# FRONT-UNIT-3_2-WIDE.net
KiCad netlist of a schematic drawn in Altium Designer
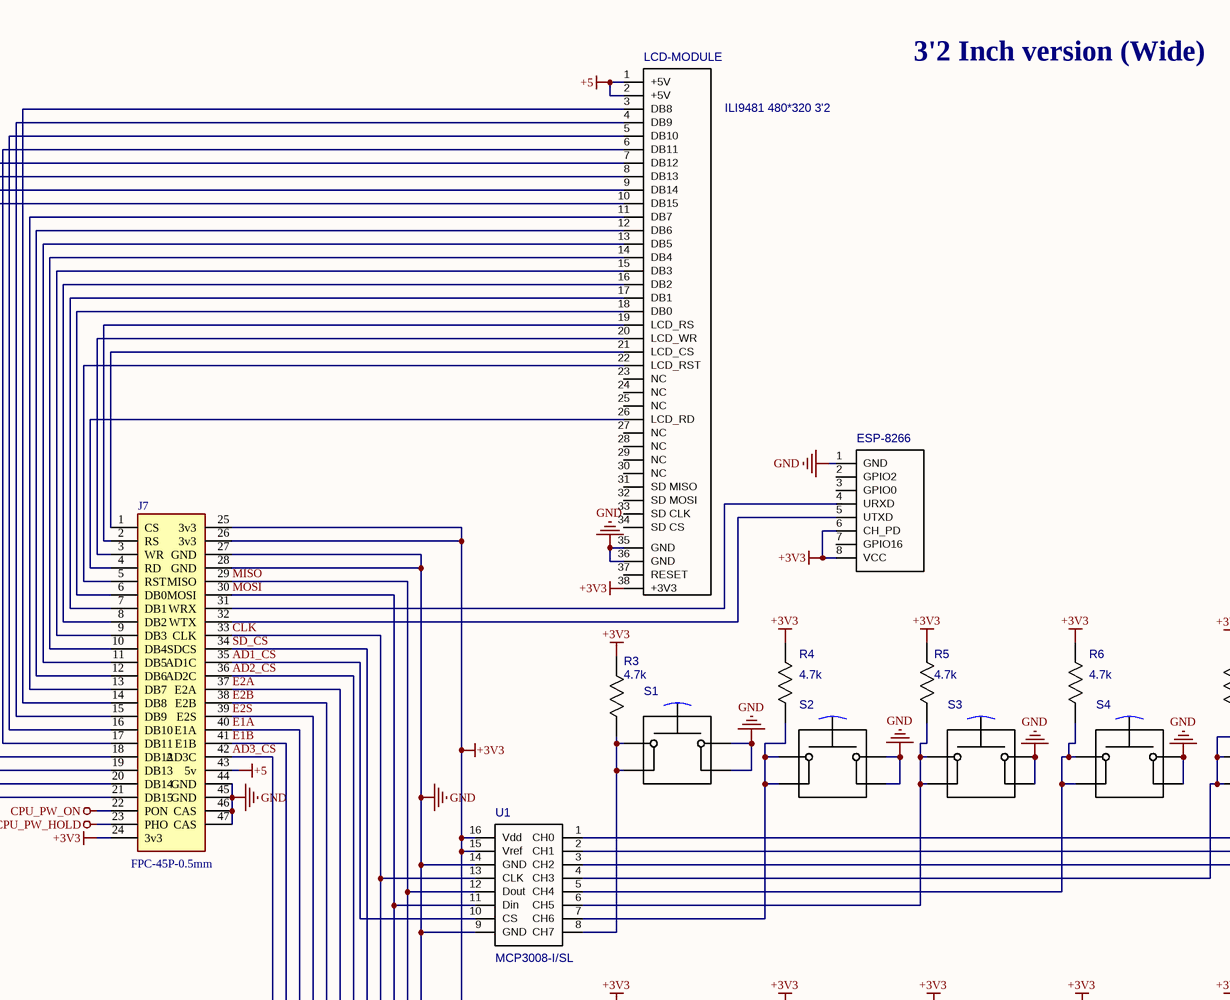
[diagram p0: FRONT-UNIT-3.2-WIDE.SCHDOC, top left]
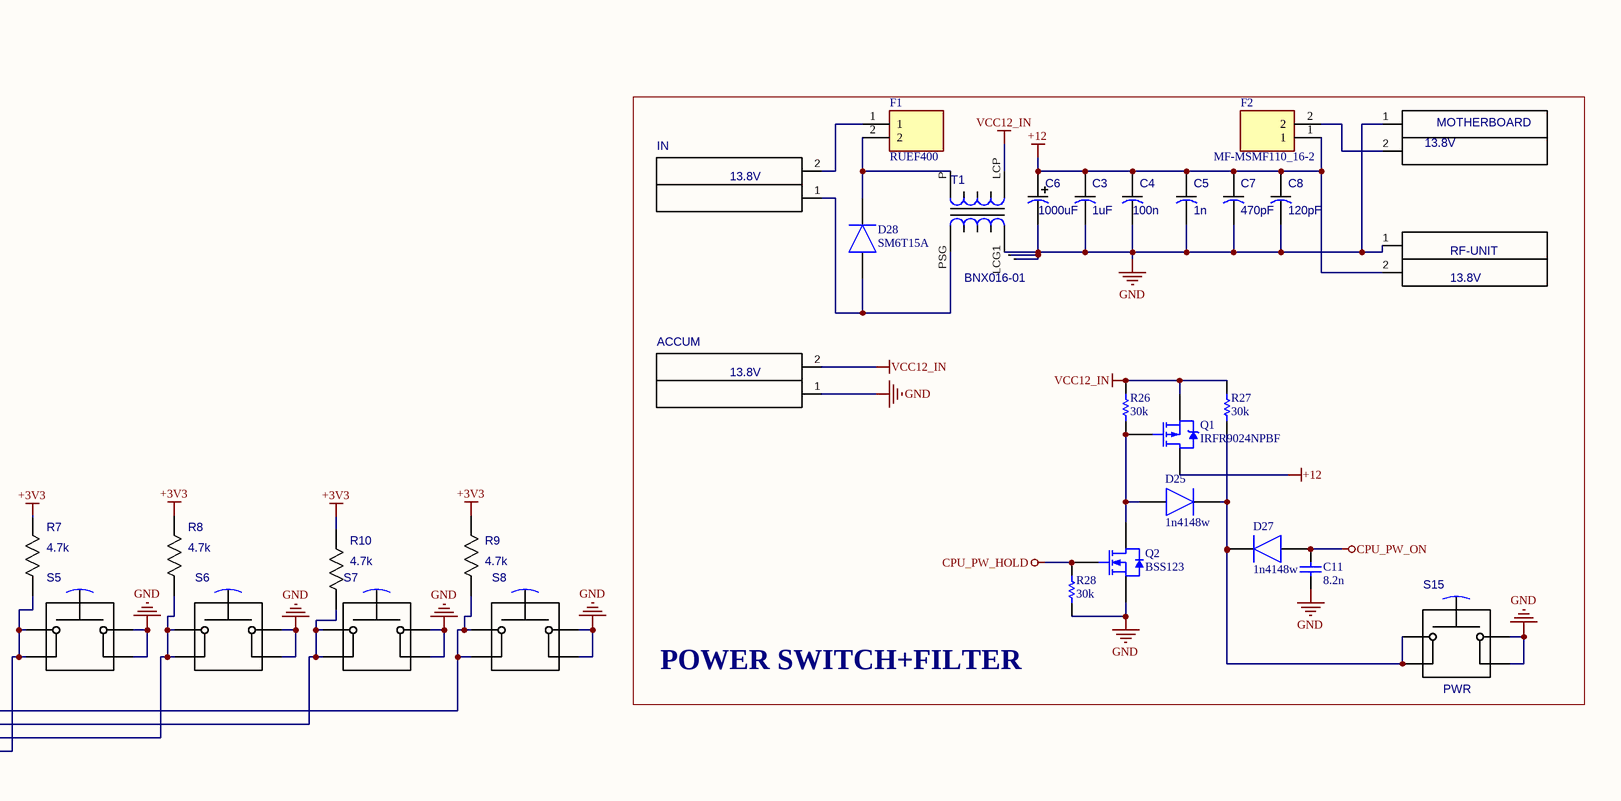
[diagram p1: FRONT-UNIT-3.2-WIDE.SCHDOC, top right]
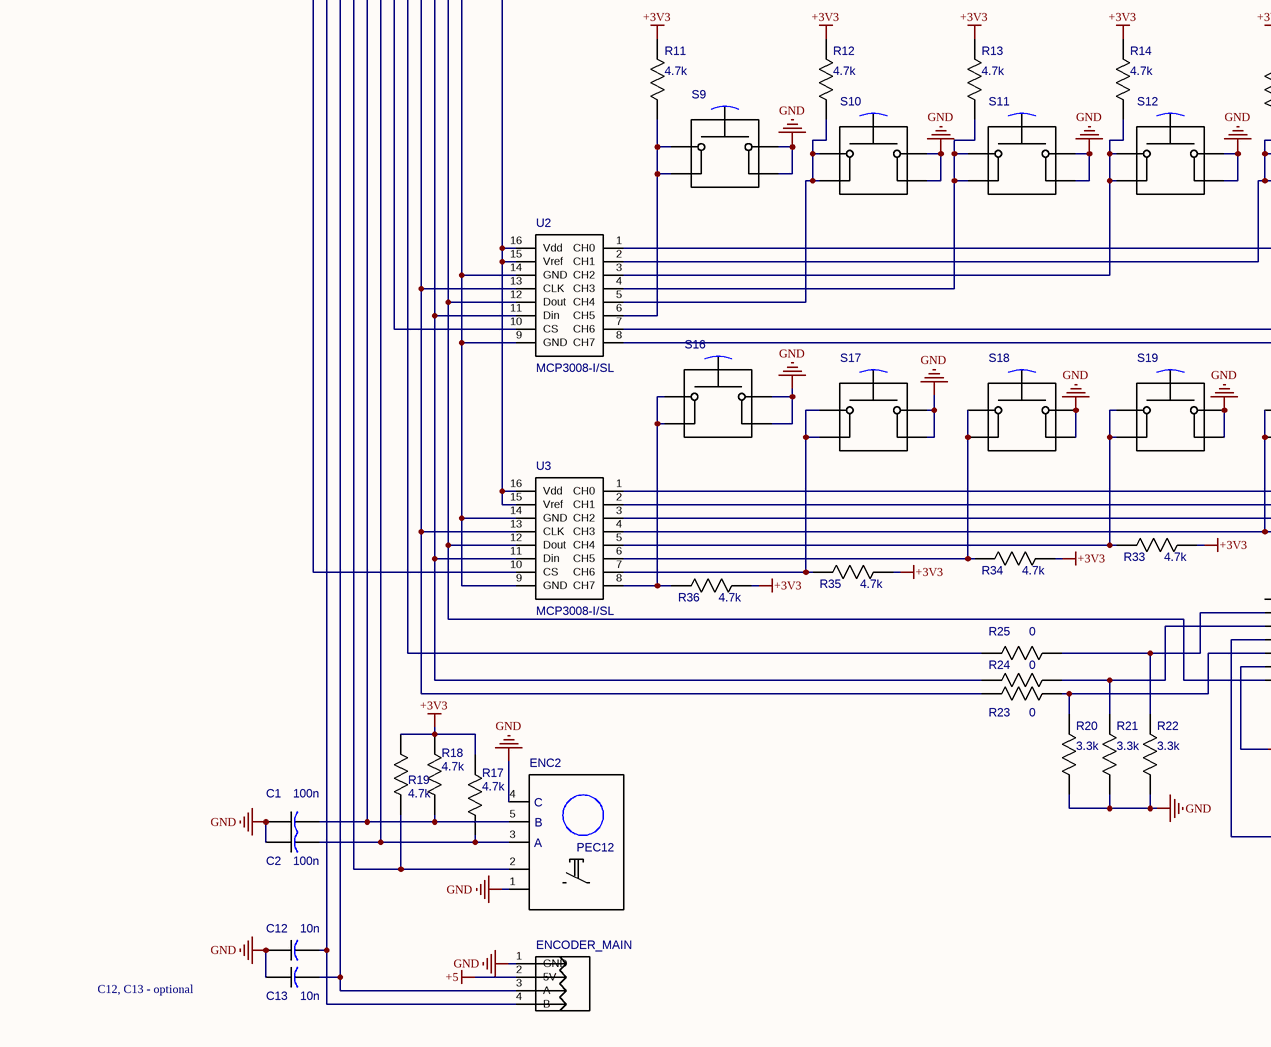
[diagram p2: FRONT-UNIT-3.2-WIDE.SCHDOC, bottom left]
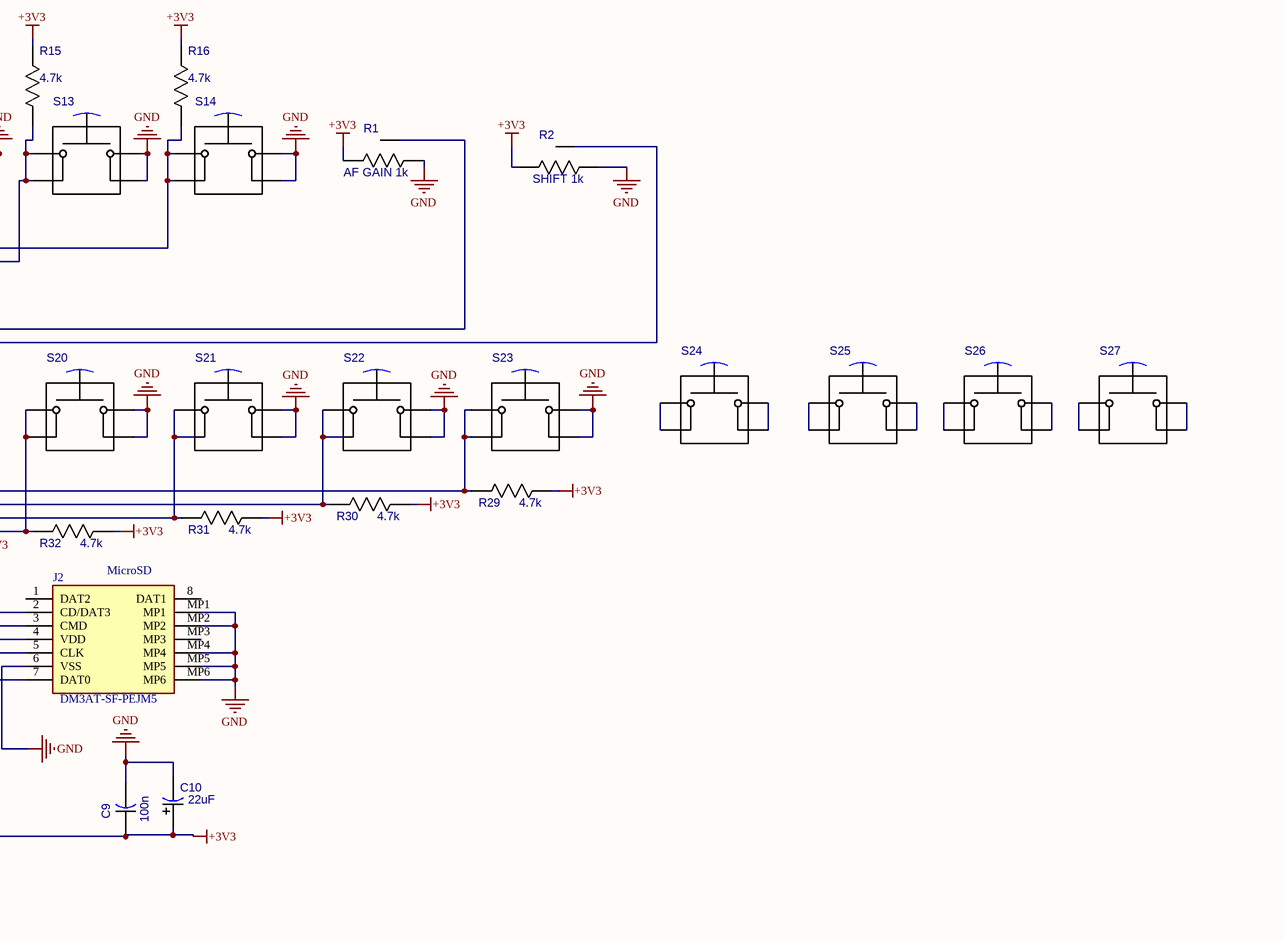
[diagram p3: FRONT-UNIT-3.2-WIDE.SCHDOC, bottom right]

(export (version "E")
  (design (tool "Eeschema 10.0.6"))
  (components
    (comp (ref "ACCUM")
      (value "13.8V")
      (footprint "JX2")
      (description "JX2")
      (libsource (lib "*") (part "JX2"))
    )
    (comp (ref "C1")
      (value "100n")
      (footprint "CAP_0805")
      (description "CAP_0805")
      (libsource (lib "*") (part "CAP_0805"))
    )
    (comp (ref "C2")
      (value "100n")
      (footprint "CAP_0805")
      (description "CAP_0805")
      (libsource (lib "*") (part "CAP_0805"))
    )
    (comp (ref "C3")
      (value "1uF")
      (footprint "CAP_1206")
      (description "CAP_1206")
      (libsource (lib "*") (part "CAP_1206"))
    )
    (comp (ref "C4")
      (value "100n")
      (footprint "CAP_1206")
      (description "CAP_1206")
      (libsource (lib "*") (part "CAP_1206"))
    )
    (comp (ref "C5")
      (value "1n")
      (footprint "CAP_1206")
      (description "CAP_1206")
      (libsource (lib "*") (part "CAP_1206"))
    )
    (comp (ref "C6")
      (value "1000uF")
      (footprint "CAP250RP")
      (description "CAP250RP")
      (libsource (lib "*") (part "CAP250RP"))
    )
    (comp (ref "C7")
      (value "470pF")
      (footprint "CAP_1206")
      (description "CAP_1206")
      (libsource (lib "*") (part "CAP_1206"))
    )
    (comp (ref "C8")
      (value "120pF")
      (footprint "CAP_1206")
      (description "CAP_1206")
      (libsource (lib "*") (part "CAP_1206"))
    )
    (comp (ref "C9")
      (value "100n")
      (footprint "CAP_0805")
      (description "CAP_0805")
      (libsource (lib "*") (part "CAP_0805"))
    )
    (comp (ref "C10")
      (value "22uF")
      (footprint "EEEFC_sizeB")
      (description "EEEFC_sizeB")
      (libsource (lib "*") (part "EEEFC_sizeB"))
    )
    (comp (ref "C11")
      (value "8.2n")
      (footprint "CAPC2013X94X50LL20T25")
      (description "CAP_1206")
      (fields
        (field (name "MANUFACTURER") "AVX Interconnect / Elco")
        (field (name "PART NUMBER") "08055C822KAT2A")
      )
      (libsource (lib "Altium Content Vault") (part "CAP"))
    )
    (comp (ref "C12")
      (value "10n")
      (footprint "CAP_0805")
      (description "CAP_0805")
      (libsource (lib "*") (part "CAP_0805"))
    )
    (comp (ref "C13")
      (value "10n")
      (footprint "CAP_0805")
      (description "CAP_0805")
      (libsource (lib "*") (part "CAP_0805"))
    )
    (comp (ref "D25")
      (value "1n4148w")
      (footprint "SamacSys:SOD3716X135N")
      (description "Diode")
      (libsource (lib "*") (part "1n4148w"))
    )
    (comp (ref "D27")
      (value "1n4148w")
      (footprint "SamacSys:SOD3716X135N")
      (description "Diode")
      (libsource (lib "*") (part "1n4148w"))
    )
    (comp (ref "D28")
      (value "SM6T15A")
      (footprint "SamacSys:SMBJ36CATR")
      (description "Diode")
      (fields (field (name "MOUSER PART NUMBER") "511-SM6T15A") (field (name "RS PART NUMBER") "4864915P"))
      (libsource (lib "*") (part "SM6T15A"))
    )
    (comp (ref "ENC2") (value "PEC12") (footprint "PEC12") (libsource (lib "*") (part "PEC12")))
    (comp (ref "ENCODER_MAIN")
      (value "OPTICAL ENCODER")
      (footprint "644456-4")
      (libsource (lib "*") (part "644456-4"))
    )
    (comp (ref "ESP-8266")
      (value "ESP-01 ESP8266")
      (footprint "ESP-01 ESP8266")
      (libsource (lib "*") (part "ESP-01 ESP8266"))
    )
    (comp (ref "F1")
      (value "RUEF400")
      (footprint "SamacSys:RUEF400")
      (description "Fuse")
      (fields (field (name "MOUSER PART NUMBER") "650-RUEF400") (field (name "RS PART NUMBER") "5176837P"))
      (libsource (lib "*") (part "RUEF400"))
    )
    (comp (ref "F2")
      (value "MF-MSMF110_16-2")
      (footprint "SamacSys:FUSC4632X85N")
      (description "Fuse")
      (fields
        (field (name "MANUFACTURER_PART_NUMBER") "MF-MSMF110/16-2")
        (field (name "MOUSER PART NUMBER") "652-MF-MSMF110/16-2")
      )
      (libsource (lib "*") (part "MF-MSMF110_16-2"))
    )
    (comp (ref "IN") (value "13.8V") (footprint "JX2") (description "JX2") (libsource (lib "*") (part "JX2")))
    (comp (ref "J2")
      (value "DM3AT-SF-PEJM5")
      (footprint "SamacSys:DM3ATSFPEJM5")
      (description "Connector")
      (libsource (lib "*") (part "DM3AT-SF-PEJM5"))
    )
    (comp (ref "J7")
      (value "FPC-45P-0.5mm")
      (footprint "FRONT-UNIT-WIDE:FH12S45S05SH60")
      (description "Connector")
      (fields
        (field (name "MANUFACTURER_PART_NUMBER") "FH12S-45S-0.5SH(55)")
        (field (name "MOUSER PART NUMBER") "798-FH12S-45S-05SH55")
      )
      (libsource (lib "*") (part "FH12S-45S-0.5SH_55_"))
    )
    (comp (ref "LCD-MODULE")
      (value "ILI9481 480*320 3'2")
      (footprint "LCD-MODULE-3.2-480-320")
      (description "LCD-MODULE_3'2_480х320")
      (libsource (lib "FRONT-UNIT") (part "LCD-MODULE_3'2_480х320"))
    )
    (comp (ref "MOTHERBOARD")
      (value "13.8V")
      (footprint "JX2")
      (description "JX2")
      (libsource (lib "*") (part "JX2"))
    )
    (comp (ref "Q1")
      (value "IRFR9024NPBF")
      (footprint "ONSC-DPAK-3-369C-01_V")
      (description "IRFR9024NPBF, Транзистор, Р-канал 55В 11А")
      (fields (field (name "MANUFACTURER") "On Semiconductor") (field (name "PARTNUMBER") "NTD2955G"))
      (libsource (lib "Altium Content Vault") (part "ONSC-PMOS-G1S3D4-3_B"))
    )
    (comp (ref "Q2")
      (value "BSS123")
      (footprint "FAIR-SOT23-3_V")
      (fields (field (name "MANUFACTURER") "Fairchild"))
      (libsource (lib "Altium Content Vault") (part "NEMOS-GSD-3"))
    )
    (comp (ref "R1")
      (value "AF GAIN 1k")
      (footprint "PTV09")
      (description "Adjustable Resistor PTV09")
      (fields (field (name "Comment") "ptv09a-4225f-b102"))
      (libsource (lib "*") (part "PTV09"))
    )
    (comp (ref "R2")
      (value "SHIFT 1k")
      (footprint "PTV09")
      (description "Adjustable Resistor PTV09")
      (fields (field (name "Comment") "ptv09a-4225f-b102"))
      (libsource (lib "*") (part "PTV09"))
    )
    (comp (ref "R3")
      (value "4.7k")
      (footprint "RES_0805")
      (description "RES_0805")
      (libsource (lib "*") (part "RES_0805"))
    )
    (comp (ref "R4")
      (value "4.7k")
      (footprint "RES_0805")
      (description "RES_0805")
      (libsource (lib "*") (part "RES_0805"))
    )
    (comp (ref "R5")
      (value "4.7k")
      (footprint "RES_0805")
      (description "RES_0805")
      (libsource (lib "*") (part "RES_0805"))
    )
    (comp (ref "R6")
      (value "4.7k")
      (footprint "RES_0805")
      (description "RES_0805")
      (libsource (lib "*") (part "RES_0805"))
    )
    (comp (ref "R7")
      (value "4.7k")
      (footprint "RES_0805")
      (description "RES_0805")
      (libsource (lib "*") (part "RES_0805"))
    )
    (comp (ref "R8")
      (value "4.7k")
      (footprint "RES_0805")
      (description "RES_0805")
      (libsource (lib "*") (part "RES_0805"))
    )
    (comp (ref "R9")
      (value "4.7k")
      (footprint "RES_0805")
      (description "RES_0805")
      (libsource (lib "*") (part "RES_0805"))
    )
    (comp (ref "R10")
      (value "4.7k")
      (footprint "RES_0805")
      (description "RES_0805")
      (libsource (lib "*") (part "RES_0805"))
    )
    (comp (ref "R11")
      (value "4.7k")
      (footprint "RES_0805")
      (description "RES_0805")
      (libsource (lib "*") (part "RES_0805"))
    )
    (comp (ref "R12")
      (value "4.7k")
      (footprint "RES_0805")
      (description "RES_0805")
      (libsource (lib "*") (part "RES_0805"))
    )
    (comp (ref "R13")
      (value "4.7k")
      (footprint "RES_0805")
      (description "RES_0805")
      (libsource (lib "*") (part "RES_0805"))
    )
    (comp (ref "R14")
      (value "4.7k")
      (footprint "RES_0805")
      (description "RES_0805")
      (libsource (lib "*") (part "RES_0805"))
    )
    (comp (ref "R15")
      (value "4.7k")
      (footprint "RES_0805")
      (description "RES_0805")
      (libsource (lib "*") (part "RES_0805"))
    )
    (comp (ref "R16")
      (value "4.7k")
      (footprint "RES_0805")
      (description "RES_0805")
      (libsource (lib "*") (part "RES_0805"))
    )
    (comp (ref "R17")
      (value "4.7k")
      (footprint "RES_0805")
      (description "RES_0805")
      (libsource (lib "*") (part "RES_0805"))
    )
    (comp (ref "R18")
      (value "4.7k")
      (footprint "RES_0805")
      (description "RES_0805")
      (libsource (lib "*") (part "RES_0805"))
    )
    (comp (ref "R19")
      (value "4.7k")
      (footprint "RES_0805")
      (description "RES_0805")
      (libsource (lib "*") (part "RES_0805"))
    )
    (comp (ref "R20")
      (value "3.3k")
      (footprint "RES_0805")
      (description "RES_0805")
      (libsource (lib "*") (part "RES_0805"))
    )
    (comp (ref "R21")
      (value "3.3k")
      (footprint "RES_0805")
      (description "RES_0805")
      (libsource (lib "*") (part "RES_0805"))
    )
    (comp (ref "R22")
      (value "3.3k")
      (footprint "RES_0805")
      (description "RES_0805")
      (libsource (lib "*") (part "RES_0805"))
    )
    (comp (ref "R23")
      (value "0")
      (footprint "RES_0805")
      (description "RES_0805")
      (libsource (lib "*") (part "RES_0805"))
    )
    (comp (ref "R24")
      (value "0")
      (footprint "RES_0805")
      (description "RES_0805")
      (libsource (lib "*") (part "RES_0805"))
    )
    (comp (ref "R25")
      (value "0")
      (footprint "RES_0805")
      (description "RES_0805")
      (libsource (lib "*") (part "RES_0805"))
    )
    (comp (ref "R26")
      (value "30k")
      (footprint "RESC2013X60X40NL20T25")
      (description "RES_0805")
      (fields (field (name "MANUFACTURER") "Panasonic") (field (name "PART NUMBER") "ERA-6AEB303V"))
      (libsource (lib "Altium Content Vault") (part "RES"))
    )
    (comp (ref "R27")
      (value "30k")
      (footprint "RESC2013X60X40NL20T25")
      (description "RES_0805")
      (fields (field (name "MANUFACTURER") "Panasonic") (field (name "PART NUMBER") "ERA-6AEB303V"))
      (libsource (lib "Altium Content Vault") (part "RES"))
    )
    (comp (ref "R28")
      (value "30k")
      (footprint "RESC2013X60X40NL20T25")
      (description "RES_0805")
      (fields (field (name "MANUFACTURER") "Panasonic") (field (name "PART NUMBER") "ERA-6AEB303V"))
      (libsource (lib "Altium Content Vault") (part "RES"))
    )
    (comp (ref "R29")
      (value "4.7k")
      (footprint "RES_0805")
      (description "RES_0805")
      (libsource (lib "*") (part "RES_0805"))
    )
    (comp (ref "R30")
      (value "4.7k")
      (footprint "RES_0805")
      (description "RES_0805")
      (libsource (lib "*") (part "RES_0805"))
    )
    (comp (ref "R31")
      (value "4.7k")
      (footprint "RES_0805")
      (description "RES_0805")
      (libsource (lib "*") (part "RES_0805"))
    )
    (comp (ref "R32")
      (value "4.7k")
      (footprint "RES_0805")
      (description "RES_0805")
      (libsource (lib "*") (part "RES_0805"))
    )
    (comp (ref "R33")
      (value "4.7k")
      (footprint "RES_0805")
      (description "RES_0805")
      (libsource (lib "*") (part "RES_0805"))
    )
    (comp (ref "R34")
      (value "4.7k")
      (footprint "RES_0805")
      (description "RES_0805")
      (libsource (lib "*") (part "RES_0805"))
    )
    (comp (ref "R35")
      (value "4.7k")
      (footprint "RES_0805")
      (description "RES_0805")
      (libsource (lib "*") (part "RES_0805"))
    )
    (comp (ref "R36")
      (value "4.7k")
      (footprint "RES_0805")
      (description "RES_0805")
      (libsource (lib "*") (part "RES_0805"))
    )
    (comp (ref "RF-UNIT")
      (value "13.8V")
      (footprint "JX2")
      (description "JX2")
      (libsource (lib "*") (part "JX2"))
    )
    (comp (ref "S1")
      (value "PTS645SK50LFS")
      (footprint "PTS645SK50LFS")
      (fields (field (name "LCSC PART #") "test"))
      (libsource (lib "*") (part "PTS645SK50LFS"))
    )
    (comp (ref "S2")
      (value "PTS645SK50LFS")
      (footprint "PTS645SK50LFS")
      (libsource (lib "*") (part "PTS645SK50LFS"))
    )
    (comp (ref "S3")
      (value "PTS645SK50LFS")
      (footprint "PTS645SK50LFS")
      (libsource (lib "*") (part "PTS645SK50LFS"))
    )
    (comp (ref "S4")
      (value "PTS645SK50LFS")
      (footprint "PTS645SK50LFS")
      (libsource (lib "*") (part "PTS645SK50LFS"))
    )
    (comp (ref "S5")
      (value "PTS645SK50LFS")
      (footprint "PTS645SK50LFS")
      (libsource (lib "*") (part "PTS645SK50LFS"))
    )
    (comp (ref "S6")
      (value "PTS645SK50LFS")
      (footprint "PTS645SK50LFS")
      (libsource (lib "*") (part "PTS645SK50LFS"))
    )
    (comp (ref "S7")
      (value "PTS645SK50LFS")
      (footprint "PTS645SK50LFS")
      (libsource (lib "*") (part "PTS645SK50LFS"))
    )
    (comp (ref "S8")
      (value "PTS645SK50LFS")
      (footprint "PTS645SK50LFS")
      (libsource (lib "*") (part "PTS645SK50LFS"))
    )
    (comp (ref "S9")
      (value "PTS645SK50LFS")
      (footprint "PTS645SK50LFS")
      (libsource (lib "*") (part "PTS645SK50LFS"))
    )
    (comp (ref "S10")
      (value "PTS645SK50LFS")
      (footprint "PTS645SK50LFS")
      (libsource (lib "*") (part "PTS645SK50LFS"))
    )
    (comp (ref "S11")
      (value "PTS645SK50LFS")
      (footprint "PTS645SK50LFS")
      (libsource (lib "*") (part "PTS645SK50LFS"))
    )
    (comp (ref "S12")
      (value "PTS645SK50LFS")
      (footprint "PTS645SK50LFS")
      (libsource (lib "*") (part "PTS645SK50LFS"))
    )
    (comp (ref "S13")
      (value "PTS645SK50LFS")
      (footprint "PTS645SK50LFS")
      (libsource (lib "*") (part "PTS645SK50LFS"))
    )
    (comp (ref "S14")
      (value "PTS645SK50LFS")
      (footprint "PTS645SK50LFS")
      (libsource (lib "*") (part "PTS645SK50LFS"))
    )
    (comp (ref "S15")
      (value "PWR")
      (footprint "PTS645SK50LFS")
      (description "PTS645SK50LFS")
      (libsource (lib "*") (part "PTS645SK50LFS"))
    )
    (comp (ref "S16")
      (value "PTS645SK50LFS")
      (footprint "PTS645SK50LFS")
      (libsource (lib "*") (part "PTS645SK50LFS"))
    )
    (comp (ref "S17")
      (value "PTS645SK50LFS")
      (footprint "PTS645SK50LFS")
      (libsource (lib "*") (part "PTS645SK50LFS"))
    )
    (comp (ref "S18")
      (value "PTS645SK50LFS")
      (footprint "PTS645SK50LFS")
      (libsource (lib "*") (part "PTS645SK50LFS"))
    )
    (comp (ref "S19")
      (value "PTS645SK50LFS")
      (footprint "PTS645SK50LFS")
      (libsource (lib "*") (part "PTS645SK50LFS"))
    )
    (comp (ref "S20")
      (value "PTS645SK50LFS")
      (footprint "PTS645SK50LFS")
      (libsource (lib "*") (part "PTS645SK50LFS"))
    )
    (comp (ref "S21")
      (value "PTS645SK50LFS")
      (footprint "PTS645SK50LFS")
      (libsource (lib "*") (part "PTS645SK50LFS"))
    )
    (comp (ref "S22")
      (value "PTS645SK50LFS")
      (footprint "PTS645SK50LFS")
      (libsource (lib "*") (part "PTS645SK50LFS"))
    )
    (comp (ref "S23")
      (value "PTS645SK50LFS")
      (footprint "PTS645SK50LFS")
      (libsource (lib "*") (part "PTS645SK50LFS"))
    )
    (comp (ref "S24")
      (value "PTS645SK50LFS")
      (footprint "PTS645SK50LFS")
      (libsource (lib "*") (part "PTS645SK50LFS"))
    )
    (comp (ref "S25")
      (value "PTS645SK50LFS")
      (footprint "PTS645SK50LFS")
      (libsource (lib "*") (part "PTS645SK50LFS"))
    )
    (comp (ref "S26")
      (value "PTS645SK50LFS")
      (footprint "PTS645SK50LFS")
      (libsource (lib "*") (part "PTS645SK50LFS"))
    )
    (comp (ref "S27")
      (value "PTS645SK50LFS")
      (footprint "PTS645SK50LFS")
      (libsource (lib "*") (part "PTS645SK50LFS"))
    )
    (comp (ref "T1")
      (value "BNX016-01")
      (footprint "TRANSF_ICORE")
      (libsource (lib "*") (part "TRANSF_ICORE"))
    )
    (comp (ref "U1")
      (value "MCP3008-I/SL")
      (footprint "MCP3008-I/SL")
      (libsource (lib "*") (part "MCP3008-I/SL"))
    )
    (comp (ref "U2")
      (value "MCP3008-I/SL")
      (footprint "MCP3008-I/SL")
      (libsource (lib "*") (part "MCP3008-I/SL"))
    )
    (comp (ref "U3")
      (value "MCP3008-I/SL")
      (footprint "MCP3008-I/SL")
      (libsource (lib "*") (part "MCP3008-I/SL"))
    )
  )
  (nets
    (net (code "1") (name "+3V3") (class "Default")
      (node (ref "C10") (pin "1") (pinfunction "PLUS_1") (pintype "passive"))
      (node (ref "C9") (pin "1") (pinfunction "1_1") (pintype "passive"))
      (node (ref "ESP-8266") (pin "6") (pinfunction "CH_PD_6") (pintype "passive"))
      (node (ref "ESP-8266") (pin "8") (pinfunction "VCC_8") (pintype "passive"))
      (node (ref "J2") (pin "4") (pinfunction "VDD_4") (pintype "passive"))
      (node (ref "J7") (pin "24") (pinfunction "3v3_24") (pintype "passive"))
      (node (ref "J7") (pin "25") (pinfunction "3v3_25") (pintype "passive"))
      (node (ref "J7") (pin "26") (pinfunction "3v3_26") (pintype "passive"))
      (node (ref "LCD-MODULE") (pin "38") (pinfunction "+3V3_38") (pintype "passive"))
      (node (ref "R1") (pin "1") (pinfunction "CW_1") (pintype "passive"))
      (node (ref "R10") (pin "2") (pinfunction "2_2") (pintype "passive"))
      (node (ref "R11") (pin "2") (pinfunction "2_2") (pintype "passive"))
      (node (ref "R12") (pin "2") (pinfunction "2_2") (pintype "passive"))
      (node (ref "R13") (pin "2") (pinfunction "2_2") (pintype "passive"))
      (node (ref "R14") (pin "2") (pinfunction "2_2") (pintype "passive"))
      (node (ref "R15") (pin "2") (pinfunction "2_2") (pintype "passive"))
      (node (ref "R16") (pin "2") (pinfunction "2_2") (pintype "passive"))
      (node (ref "R17") (pin "2") (pinfunction "2_2") (pintype "passive"))
      (node (ref "R18") (pin "2") (pinfunction "2_2") (pintype "passive"))
      (node (ref "R19") (pin "2") (pinfunction "2_2") (pintype "passive"))
      (node (ref "R2") (pin "1") (pinfunction "CW_1") (pintype "passive"))
      (node (ref "R29") (pin "2") (pinfunction "2_2") (pintype "passive"))
      (node (ref "R3") (pin "2") (pinfunction "2_2") (pintype "passive"))
      (node (ref "R30") (pin "2") (pinfunction "2_2") (pintype "passive"))
      (node (ref "R31") (pin "2") (pinfunction "2_2") (pintype "passive"))
      (node (ref "R32") (pin "2") (pinfunction "2_2") (pintype "passive"))
      (node (ref "R33") (pin "2") (pinfunction "2_2") (pintype "passive"))
      (node (ref "R34") (pin "2") (pinfunction "2_2") (pintype "passive"))
      (node (ref "R35") (pin "2") (pinfunction "2_2") (pintype "passive"))
      (node (ref "R36") (pin "2") (pinfunction "2_2") (pintype "passive"))
      (node (ref "R4") (pin "2") (pinfunction "2_2") (pintype "passive"))
      (node (ref "R5") (pin "2") (pinfunction "2_2") (pintype "passive"))
      (node (ref "R6") (pin "2") (pinfunction "2_2") (pintype "passive"))
      (node (ref "R7") (pin "2") (pinfunction "2_2") (pintype "passive"))
      (node (ref "R8") (pin "2") (pinfunction "2_2") (pintype "passive"))
      (node (ref "R9") (pin "2") (pinfunction "2_2") (pintype "passive"))
      (node (ref "U1") (pin "15") (pinfunction "Vref_15") (pintype "passive"))
      (node (ref "U1") (pin "16") (pinfunction "Vdd_16") (pintype "passive"))
      (node (ref "U2") (pin "15") (pinfunction "Vref_15") (pintype "passive"))
      (node (ref "U2") (pin "16") (pinfunction "Vdd_16") (pintype "passive"))
      (node (ref "U3") (pin "15") (pinfunction "Vref_15") (pintype "passive"))
      (node (ref "U3") (pin "16") (pinfunction "Vdd_16") (pintype "passive"))
    )
    (net (code "2") (name "+5") (class "Default")
      (node (ref "ENCODER_MAIN") (pin "2") (pinfunction "5V_2") (pintype "passive"))
      (node (ref "J7") (pin "43") (pinfunction "5v_43") (pintype "passive"))
      (node (ref "LCD-MODULE") (pin "1") (pinfunction "+5V_1") (pintype "passive"))
      (node (ref "LCD-MODULE") (pin "2") (pinfunction "+5V_2") (pintype "passive"))
    )
    (net (code "3") (name "+12") (class "Default")
      (node (ref "C3") (pin "1") (pinfunction "1_1") (pintype "passive"))
      (node (ref "C4") (pin "1") (pinfunction "1_1") (pintype "passive"))
      (node (ref "C5") (pin "1") (pinfunction "1_1") (pintype "passive"))
      (node (ref "C6") (pin "1") (pinfunction "PLUS_1") (pintype "passive"))
      (node (ref "C7") (pin "1") (pinfunction "1_1") (pintype "passive"))
      (node (ref "C8") (pin "1") (pinfunction "1_1") (pintype "passive"))
      (node (ref "F2") (pin "1") (pinfunction "1_1") (pintype "passive"))
      (node (ref "Q1") (pin "4") (pinfunction "D_4") (pintype "passive"))
      (node (ref "RF-UNIT") (pin "2") (pinfunction "2_2") (pintype "passive"))
    )
    (net (code "4") (name "/AD1_CS") (class "Default")
      (node (ref "J7") (pin "35") (pinfunction "AD1C_35") (pintype "passive"))
      (node (ref "U1") (pin "10") (pinfunction "CS_10") (pintype "passive"))
    )
    (net (code "5") (name "/AD2_CS") (class "Default")
      (node (ref "J7") (pin "36") (pinfunction "AD2C_36") (pintype "passive"))
      (node (ref "U2") (pin "10") (pinfunction "CS_10") (pintype "passive"))
    )
    (net (code "6") (name "/AD3_CS") (class "Default")
      (node (ref "J7") (pin "42") (pinfunction "AD3C_42") (pintype "passive"))
      (node (ref "U3") (pin "10") (pinfunction "CS_10") (pintype "passive"))
    )
    (net (code "7") (name "/CLK") (class "Default")
      (node (ref "J7") (pin "33") (pinfunction "CLK_33") (pintype "passive"))
      (node (ref "R23") (pin "2") (pinfunction "2_2") (pintype "passive"))
      (node (ref "U1") (pin "13") (pinfunction "CLK_13") (pintype "passive"))
      (node (ref "U2") (pin "13") (pinfunction "CLK_13") (pintype "passive"))
      (node (ref "U3") (pin "13") (pinfunction "CLK_13") (pintype "passive"))
    )
    (net (code "8") (name "/E1A") (class "Default")
      (node (ref "C13") (pin "2") (pinfunction "2_2") (pintype "passive"))
      (node (ref "ENCODER_MAIN") (pin "3") (pinfunction "A_3") (pintype "passive"))
      (node (ref "J7") (pin "40") (pinfunction "E1A_40") (pintype "passive"))
    )
    (net (code "9") (name "/E1B") (class "Default")
      (node (ref "C12") (pin "2") (pinfunction "2_2") (pintype "passive"))
      (node (ref "ENCODER_MAIN") (pin "4") (pinfunction "B_4") (pintype "passive"))
      (node (ref "J7") (pin "41") (pinfunction "E1B_41") (pintype "passive"))
    )
    (net (code "10") (name "/E2A") (class "Default")
      (node (ref "C2") (pin "2") (pinfunction "2_2") (pintype "passive"))
      (node (ref "ENC2") (pin "3") (pinfunction "A_3") (pintype "passive"))
      (node (ref "J7") (pin "37") (pinfunction "E2A_37") (pintype "passive"))
      (node (ref "R17") (pin "1") (pinfunction "1_1") (pintype "passive"))
    )
    (net (code "11") (name "/E2B") (class "Default")
      (node (ref "C1") (pin "2") (pinfunction "2_2") (pintype "passive"))
      (node (ref "ENC2") (pin "5") (pinfunction "B_5") (pintype "passive"))
      (node (ref "J7") (pin "38") (pinfunction "E2B_38") (pintype "passive"))
      (node (ref "R18") (pin "1") (pinfunction "1_1") (pintype "passive"))
    )
    (net (code "12") (name "/E2S") (class "Default")
      (node (ref "ENC2") (pin "2") (pinfunction "2_2") (pintype "passive"))
      (node (ref "J7") (pin "39") (pinfunction "E2S_39") (pintype "passive"))
      (node (ref "R19") (pin "1") (pinfunction "1_1") (pintype "passive"))
    )
    (net (code "13") (name "/MISO") (class "Default")
      (node (ref "J2") (pin "7") (pinfunction "DAT0_7") (pintype "passive"))
      (node (ref "J7") (pin "29") (pinfunction "MISO_29") (pintype "passive"))
      (node (ref "U1") (pin "12") (pinfunction "Dout_12") (pintype "passive"))
      (node (ref "U2") (pin "12") (pinfunction "Dout_12") (pintype "passive"))
      (node (ref "U3") (pin "12") (pinfunction "Dout_12") (pintype "passive"))
    )
    (net (code "14") (name "/MOSI") (class "Default")
      (node (ref "J7") (pin "30") (pinfunction "MOSI_30") (pintype "passive"))
      (node (ref "R24") (pin "2") (pinfunction "2_2") (pintype "passive"))
      (node (ref "U1") (pin "11") (pinfunction "Din_11") (pintype "passive"))
      (node (ref "U2") (pin "11") (pinfunction "Din_11") (pintype "passive"))
      (node (ref "U3") (pin "11") (pinfunction "Din_11") (pintype "passive"))
    )
    (net (code "15") (name "/SD_CS") (class "Default")
      (node (ref "J7") (pin "34") (pinfunction "SDCS_34") (pintype "passive"))
      (node (ref "R25") (pin "2") (pinfunction "2_2") (pintype "passive"))
    )
    (net (code "16") (name "CPU_PW_HOLD") (class "Default")
      (node (ref "J7") (pin "23") (pinfunction "PHO_23") (pintype "passive"))
      (node (ref "Q2") (pin "1") (pinfunction "G_1") (pintype "passive"))
      (node (ref "R28") (pin "2") (pinfunction "2_2") (pintype "passive"))
    )
    (net (code "17") (name "CPU_PW_ON") (class "Default")
      (node (ref "C11") (pin "2") (pinfunction "2_2") (pintype "passive"))
      (node (ref "D27") (pin "2") (pinfunction "A_2") (pintype "passive"))
      (node (ref "J7") (pin "22") (pinfunction "PON_22") (pintype "passive"))
    )
    (net (code "18") (name "GND") (class "Default")
      (node (ref "ACCUM") (pin "1") (pinfunction "1_1") (pintype "passive"))
      (node (ref "C1") (pin "1") (pinfunction "1_1") (pintype "passive"))
      (node (ref "C10") (pin "2") (pinfunction "MINUS_2") (pintype "passive"))
      (node (ref "C11") (pin "1") (pinfunction "1_1") (pintype "passive"))
      (node (ref "C12") (pin "1") (pinfunction "1_1") (pintype "passive"))
      (node (ref "C13") (pin "1") (pinfunction "1_1") (pintype "passive"))
      (node (ref "C2") (pin "1") (pinfunction "1_1") (pintype "passive"))
      (node (ref "C3") (pin "2") (pinfunction "2_2") (pintype "passive"))
      (node (ref "C4") (pin "2") (pinfunction "2_2") (pintype "passive"))
      (node (ref "C5") (pin "2") (pinfunction "2_2") (pintype "passive"))
      (node (ref "C6") (pin "2") (pinfunction "MINUS_2") (pintype "passive"))
      (node (ref "C7") (pin "2") (pinfunction "2_2") (pintype "passive"))
      (node (ref "C8") (pin "2") (pinfunction "2_2") (pintype "passive"))
      (node (ref "C9") (pin "2") (pinfunction "2_2") (pintype "passive"))
      (node (ref "ENC2") (pin "1") (pinfunction "1_1") (pintype "passive"))
      (node (ref "ENC2") (pin "4") (pinfunction "C_4") (pintype "passive"))
      (node (ref "ENCODER_MAIN") (pin "1") (pinfunction "GND_1") (pintype "passive"))
      (node (ref "ESP-8266") (pin "1") (pinfunction "GND_1") (pintype "passive"))
      (node (ref "J2") (pin "6") (pinfunction "VSS_6") (pintype "passive"))
      (node (ref "J2") (pin "MP1") (pinfunction "MP1_MP1") (pintype "passive"))
      (node (ref "J2") (pin "MP2") (pinfunction "MP2_MP2") (pintype "passive"))
      (node (ref "J2") (pin "MP4") (pinfunction "MP4_MP4") (pintype "passive"))
      (node (ref "J2") (pin "MP5") (pinfunction "MP5_MP5") (pintype "passive"))
      (node (ref "J2") (pin "MP6") (pinfunction "MP6_MP6") (pintype "passive"))
      (node (ref "J7") (pin "27") (pinfunction "GND_27") (pintype "passive"))
      (node (ref "J7") (pin "28") (pinfunction "GND_28") (pintype "passive"))
      (node (ref "J7") (pin "44") (pinfunction "GND_44") (pintype "passive"))
      (node (ref "J7") (pin "45") (pinfunction "GND_45") (pintype "passive"))
      (node (ref "J7") (pin "46") (pinfunction "CAS_46") (pintype "passive"))
      (node (ref "J7") (pin "47") (pinfunction "CAS_47") (pintype "passive"))
      (node (ref "LCD-MODULE") (pin "35") (pinfunction "GND_35") (pintype "passive"))
      (node (ref "LCD-MODULE") (pin "36") (pinfunction "GND_36") (pintype "passive"))
      (node (ref "MOTHERBOARD") (pin "1") (pinfunction "1_1") (pintype "passive"))
      (node (ref "Q2") (pin "2") (pinfunction "S_2") (pintype "passive"))
      (node (ref "R1") (pin "3") (pinfunction "CCW_3") (pintype "passive"))
      (node (ref "R2") (pin "3") (pinfunction "CCW_3") (pintype "passive"))
      (node (ref "R20") (pin "1") (pinfunction "1_1") (pintype "passive"))
      (node (ref "R21") (pin "1") (pinfunction "1_1") (pintype "passive"))
      (node (ref "R22") (pin "1") (pinfunction "1_1") (pintype "passive"))
      (node (ref "R28") (pin "1") (pinfunction "1_1") (pintype "passive"))
      (node (ref "RF-UNIT") (pin "1") (pinfunction "1_1") (pintype "passive"))
      (node (ref "S1") (pin "3") (pinfunction "B_3") (pintype "passive"))
      (node (ref "S1") (pin "4") (pinfunction "B_4") (pintype "passive"))
      (node (ref "S10") (pin "3") (pinfunction "B_3") (pintype "passive"))
      (node (ref "S10") (pin "4") (pinfunction "B_4") (pintype "passive"))
      (node (ref "S11") (pin "3") (pinfunction "B_3") (pintype "passive"))
      (node (ref "S11") (pin "4") (pinfunction "B_4") (pintype "passive"))
      (node (ref "S12") (pin "3") (pinfunction "B_3") (pintype "passive"))
      (node (ref "S12") (pin "4") (pinfunction "B_4") (pintype "passive"))
      (node (ref "S13") (pin "3") (pinfunction "B_3") (pintype "passive"))
      (node (ref "S13") (pin "4") (pinfunction "B_4") (pintype "passive"))
      (node (ref "S14") (pin "3") (pinfunction "B_3") (pintype "passive"))
      (node (ref "S14") (pin "4") (pinfunction "B_4") (pintype "passive"))
      (node (ref "S15") (pin "3") (pinfunction "B_3") (pintype "passive"))
      (node (ref "S15") (pin "4") (pinfunction "B_4") (pintype "passive"))
      (node (ref "S16") (pin "3") (pinfunction "B_3") (pintype "passive"))
      (node (ref "S16") (pin "4") (pinfunction "B_4") (pintype "passive"))
      (node (ref "S17") (pin "3") (pinfunction "B_3") (pintype "passive"))
      (node (ref "S17") (pin "4") (pinfunction "B_4") (pintype "passive"))
      (node (ref "S18") (pin "3") (pinfunction "B_3") (pintype "passive"))
      (node (ref "S18") (pin "4") (pinfunction "B_4") (pintype "passive"))
      (node (ref "S19") (pin "3") (pinfunction "B_3") (pintype "passive"))
      (node (ref "S19") (pin "4") (pinfunction "B_4") (pintype "passive"))
      (node (ref "S2") (pin "3") (pinfunction "B_3") (pintype "passive"))
      (node (ref "S2") (pin "4") (pinfunction "B_4") (pintype "passive"))
      (node (ref "S20") (pin "3") (pinfunction "B_3") (pintype "passive"))
      (node (ref "S20") (pin "4") (pinfunction "B_4") (pintype "passive"))
      (node (ref "S21") (pin "3") (pinfunction "B_3") (pintype "passive"))
      (node (ref "S21") (pin "4") (pinfunction "B_4") (pintype "passive"))
      (node (ref "S22") (pin "3") (pinfunction "B_3") (pintype "passive"))
      (node (ref "S22") (pin "4") (pinfunction "B_4") (pintype "passive"))
      (node (ref "S23") (pin "3") (pinfunction "B_3") (pintype "passive"))
      (node (ref "S23") (pin "4") (pinfunction "B_4") (pintype "passive"))
      (node (ref "S3") (pin "3") (pinfunction "B_3") (pintype "passive"))
      (node (ref "S3") (pin "4") (pinfunction "B_4") (pintype "passive"))
      (node (ref "S4") (pin "3") (pinfunction "B_3") (pintype "passive"))
      (node (ref "S4") (pin "4") (pinfunction "B_4") (pintype "passive"))
      (node (ref "S5") (pin "3") (pinfunction "B_3") (pintype "passive"))
      (node (ref "S5") (pin "4") (pinfunction "B_4") (pintype "passive"))
      (node (ref "S6") (pin "3") (pinfunction "B_3") (pintype "passive"))
      (node (ref "S6") (pin "4") (pinfunction "B_4") (pintype "passive"))
      (node (ref "S7") (pin "3") (pinfunction "B_3") (pintype "passive"))
      (node (ref "S7") (pin "4") (pinfunction "B_4") (pintype "passive"))
      (node (ref "S8") (pin "3") (pinfunction "B_3") (pintype "passive"))
      (node (ref "S8") (pin "4") (pinfunction "B_4") (pintype "passive"))
      (node (ref "S9") (pin "3") (pinfunction "B_3") (pintype "passive"))
      (node (ref "S9") (pin "4") (pinfunction "B_4") (pintype "passive"))
      (node (ref "T1") (pin "LCG1") (pinfunction "S2_LCG1") (pintype "passive"))
      (node (ref "T1") (pin "LCG2") (pinfunction "0_LCG2") (pintype "passive"))
      (node (ref "T1") (pin "LCG3") (pinfunction "0_LCG3") (pintype "passive"))
      (node (ref "U1") (pin "14") (pinfunction "GND_14") (pintype "passive"))
      (node (ref "U1") (pin "9") (pinfunction "GND_9") (pintype "passive"))
      (node (ref "U2") (pin "14") (pinfunction "GND_14") (pintype "passive"))
      (node (ref "U2") (pin "9") (pinfunction "GND_9") (pintype "passive"))
      (node (ref "U3") (pin "14") (pinfunction "GND_14") (pintype "passive"))
      (node (ref "U3") (pin "9") (pinfunction "GND_9") (pintype "passive"))
    )
    (net (code "19") (name "Net-(D25-A)") (class "Default")
      (node (ref "D25") (pin "2") (pinfunction "A_2") (pintype "passive"))
      (node (ref "Q1") (pin "1") (pinfunction "G_1") (pintype "passive"))
      (node (ref "Q2") (pin "3") (pinfunction "D_3") (pintype "passive"))
      (node (ref "R26") (pin "1") (pinfunction "1_1") (pintype "passive"))
    )
    (net (code "20") (name "Net-(D25-K)") (class "Default")
      (node (ref "D25") (pin "1") (pinfunction "K_1") (pintype "passive"))
      (node (ref "D27") (pin "1") (pinfunction "K_1") (pintype "passive"))
      (node (ref "R27") (pin "1") (pinfunction "1_1") (pintype "passive"))
      (node (ref "S15") (pin "1") (pinfunction "A_1") (pintype "passive"))
      (node (ref "S15") (pin "2") (pinfunction "A_2") (pintype "passive"))
    )
    (net (code "21") (name "Net-(D28-A)") (class "Default")
      (node (ref "D28") (pin "2") (pinfunction "A_2") (pintype "passive"))
      (node (ref "IN") (pin "1") (pinfunction "1_1") (pintype "passive"))
      (node (ref "T1") (pin "PSG") (pinfunction "S1_PSG") (pintype "passive"))
    )
    (net (code "22") (name "Net-(D28-K)") (class "Default")
      (node (ref "D28") (pin "1") (pinfunction "K_1") (pintype "passive"))
      (node (ref "F1") (pin "2") (pinfunction "2_2") (pintype "passive"))
      (node (ref "T1") (pin "P") (pinfunction "P1_P") (pintype "passive"))
    )
    (net (code "23") (name "Net-(ESP-8266-URXD)") (class "Default")
      (node (ref "ESP-8266") (pin "4") (pinfunction "URXD_4") (pintype "passive"))
      (node (ref "J7") (pin "31") (pinfunction "WRX_31") (pintype "passive"))
    )
    (net (code "24") (name "Net-(ESP-8266-UTXD)") (class "Default")
      (node (ref "ESP-8266") (pin "5") (pinfunction "UTXD_5") (pintype "passive"))
      (node (ref "J7") (pin "32") (pinfunction "WTX_32") (pintype "passive"))
    )
    (net (code "25") (name "Net-(F1-Pad1)") (class "Default")
      (node (ref "F1") (pin "1") (pinfunction "1_1") (pintype "passive"))
      (node (ref "IN") (pin "2") (pinfunction "2_2") (pintype "passive"))
    )
    (net (code "26") (name "Net-(F2-Pad2)") (class "Default")
      (node (ref "F2") (pin "2") (pinfunction "2_2") (pintype "passive"))
      (node (ref "MOTHERBOARD") (pin "2") (pinfunction "2_2") (pintype "passive"))
    )
    (net (code "27") (name "Net-(J2-CD{slash}DAT3)") (class "Default")
      (node (ref "J2") (pin "2") (pinfunction "CD/DAT3_2") (pintype "passive"))
      (node (ref "R22") (pin "2") (pinfunction "2_2") (pintype "passive"))
      (node (ref "R25") (pin "1") (pinfunction "1_1") (pintype "passive"))
    )
    (net (code "28") (name "Net-(J2-CLK)") (class "Default")
      (node (ref "J2") (pin "5") (pinfunction "CLK_5") (pintype "passive"))
      (node (ref "R20") (pin "2") (pinfunction "2_2") (pintype "passive"))
      (node (ref "R23") (pin "1") (pinfunction "1_1") (pintype "passive"))
    )
    (net (code "29") (name "Net-(J2-CMD)") (class "Default")
      (node (ref "J2") (pin "3") (pinfunction "CMD_3") (pintype "passive"))
      (node (ref "R21") (pin "2") (pinfunction "2_2") (pintype "passive"))
      (node (ref "R24") (pin "1") (pinfunction "1_1") (pintype "passive"))
    )
    (net (code "30") (name "Net-(J7-CS)") (class "Default")
      (node (ref "J7") (pin "1") (pinfunction "CS_1") (pintype "passive"))
      (node (ref "LCD-MODULE") (pin "21") (pinfunction "LCD_CS_21") (pintype "passive"))
    )
    (net (code "31") (name "Net-(J7-DB0)") (class "Default")
      (node (ref "J7") (pin "6") (pinfunction "DB0_6") (pintype "passive"))
      (node (ref "LCD-MODULE") (pin "18") (pinfunction "DB0_18") (pintype "passive"))
    )
    (net (code "32") (name "Net-(J7-DB1)") (class "Default")
      (node (ref "J7") (pin "7") (pinfunction "DB1_7") (pintype "passive"))
      (node (ref "LCD-MODULE") (pin "17") (pinfunction "DB1_17") (pintype "passive"))
    )
    (net (code "33") (name "Net-(J7-DB2)") (class "Default")
      (node (ref "J7") (pin "8") (pinfunction "DB2_8") (pintype "passive"))
      (node (ref "LCD-MODULE") (pin "16") (pinfunction "DB2_16") (pintype "passive"))
    )
    (net (code "34") (name "Net-(J7-DB3)") (class "Default")
      (node (ref "J7") (pin "9") (pinfunction "DB3_9") (pintype "passive"))
      (node (ref "LCD-MODULE") (pin "15") (pinfunction "DB3_15") (pintype "passive"))
    )
    (net (code "35") (name "Net-(J7-DB4)") (class "Default")
      (node (ref "J7") (pin "10") (pinfunction "DB4_10") (pintype "passive"))
      (node (ref "LCD-MODULE") (pin "14") (pinfunction "DB4_14") (pintype "passive"))
    )
    (net (code "36") (name "Net-(J7-DB5)") (class "Default")
      (node (ref "J7") (pin "11") (pinfunction "DB5_11") (pintype "passive"))
      (node (ref "LCD-MODULE") (pin "13") (pinfunction "DB5_13") (pintype "passive"))
    )
    (net (code "37") (name "Net-(J7-DB6)") (class "Default")
      (node (ref "J7") (pin "12") (pinfunction "DB6_12") (pintype "passive"))
      (node (ref "LCD-MODULE") (pin "12") (pinfunction "DB6_12") (pintype "passive"))
    )
    (net (code "38") (name "Net-(J7-DB7)") (class "Default")
      (node (ref "J7") (pin "13") (pinfunction "DB7_13") (pintype "passive"))
      (node (ref "LCD-MODULE") (pin "11") (pinfunction "DB7_11") (pintype "passive"))
    )
    (net (code "39") (name "Net-(J7-DB8)") (class "Default")
      (node (ref "J7") (pin "14") (pinfunction "DB8_14") (pintype "passive"))
      (node (ref "LCD-MODULE") (pin "3") (pinfunction "DB8_3") (pintype "passive"))
    )
    (net (code "40") (name "Net-(J7-DB9)") (class "Default")
      (node (ref "J7") (pin "15") (pinfunction "DB9_15") (pintype "passive"))
      (node (ref "LCD-MODULE") (pin "4") (pinfunction "DB9_4") (pintype "passive"))
    )
    (net (code "41") (name "Net-(J7-DB10)") (class "Default")
      (node (ref "J7") (pin "16") (pinfunction "DB10_16") (pintype "passive"))
      (node (ref "LCD-MODULE") (pin "5") (pinfunction "DB10_5") (pintype "passive"))
    )
    (net (code "42") (name "Net-(J7-DB11)") (class "Default")
      (node (ref "J7") (pin "17") (pinfunction "DB11_17") (pintype "passive"))
      (node (ref "LCD-MODULE") (pin "6") (pinfunction "DB11_6") (pintype "passive"))
    )
    (net (code "43") (name "Net-(J7-DB12)") (class "Default")
      (node (ref "J7") (pin "18") (pinfunction "DB12_18") (pintype "passive"))
      (node (ref "LCD-MODULE") (pin "7") (pinfunction "DB12_7") (pintype "passive"))
    )
    (net (code "44") (name "Net-(J7-DB13)") (class "Default")
      (node (ref "J7") (pin "19") (pinfunction "DB13_19") (pintype "passive"))
      (node (ref "LCD-MODULE") (pin "8") (pinfunction "DB13_8") (pintype "passive"))
    )
    (net (code "45") (name "Net-(J7-DB14)") (class "Default")
      (node (ref "J7") (pin "20") (pinfunction "DB14_20") (pintype "passive"))
      (node (ref "LCD-MODULE") (pin "9") (pinfunction "DB14_9") (pintype "passive"))
    )
    (net (code "46") (name "Net-(J7-DB15)") (class "Default")
      (node (ref "J7") (pin "21") (pinfunction "DB15_21") (pintype "passive"))
      (node (ref "LCD-MODULE") (pin "10") (pinfunction "DB15_10") (pintype "passive"))
    )
    (net (code "47") (name "Net-(J7-RD)") (class "Default")
      (node (ref "J7") (pin "4") (pinfunction "RD_4") (pintype "passive"))
      (node (ref "LCD-MODULE") (pin "26") (pinfunction "LCD_RD_26") (pintype "passive"))
    )
    (net (code "48") (name "Net-(J7-RS)") (class "Default")
      (node (ref "J7") (pin "2") (pinfunction "RS_2") (pintype "passive"))
      (node (ref "LCD-MODULE") (pin "19") (pinfunction "LCD_RS_19") (pintype "passive"))
    )
    (net (code "49") (name "Net-(J7-RST)") (class "Default")
      (node (ref "J7") (pin "5") (pinfunction "RST_5") (pintype "passive"))
      (node (ref "LCD-MODULE") (pin "22") (pinfunction "LCD_RST_22") (pintype "passive"))
    )
    (net (code "50") (name "Net-(J7-WR)") (class "Default")
      (node (ref "J7") (pin "3") (pinfunction "WR_3") (pintype "passive"))
      (node (ref "LCD-MODULE") (pin "20") (pinfunction "LCD_WR_20") (pintype "passive"))
    )
    (net (code "51") (name "Net-(R1-W)") (class "Default")
      (node (ref "R1") (pin "2") (pinfunction "W_2") (pintype "passive"))
      (node (ref "U2") (pin "7") (pinfunction "CH6_7") (pintype "passive"))
    )
    (net (code "52") (name "Net-(R2-W)") (class "Default")
      (node (ref "R2") (pin "2") (pinfunction "W_2") (pintype "passive"))
      (node (ref "U2") (pin "8") (pinfunction "CH7_8") (pintype "passive"))
    )
    (net (code "53") (name "Net-(S24-A-Pad1)") (class "Default")
      (node (ref "S24") (pin "1") (pinfunction "A_1") (pintype "passive"))
      (node (ref "S24") (pin "2") (pinfunction "A_2") (pintype "passive"))
    )
    (net (code "54") (name "Net-(S24-B-Pad3)") (class "Default")
      (node (ref "S24") (pin "3") (pinfunction "B_3") (pintype "passive"))
      (node (ref "S24") (pin "4") (pinfunction "B_4") (pintype "passive"))
    )
    (net (code "55") (name "Net-(S25-A-Pad1)") (class "Default")
      (node (ref "S25") (pin "1") (pinfunction "A_1") (pintype "passive"))
      (node (ref "S25") (pin "2") (pinfunction "A_2") (pintype "passive"))
    )
    (net (code "56") (name "Net-(S25-B-Pad3)") (class "Default")
      (node (ref "S25") (pin "3") (pinfunction "B_3") (pintype "passive"))
      (node (ref "S25") (pin "4") (pinfunction "B_4") (pintype "passive"))
    )
    (net (code "57") (name "Net-(S26-A-Pad1)") (class "Default")
      (node (ref "S26") (pin "1") (pinfunction "A_1") (pintype "passive"))
      (node (ref "S26") (pin "2") (pinfunction "A_2") (pintype "passive"))
    )
    (net (code "58") (name "Net-(S26-B-Pad3)") (class "Default")
      (node (ref "S26") (pin "3") (pinfunction "B_3") (pintype "passive"))
      (node (ref "S26") (pin "4") (pinfunction "B_4") (pintype "passive"))
    )
    (net (code "59") (name "Net-(S27-A-Pad1)") (class "Default")
      (node (ref "S27") (pin "1") (pinfunction "A_1") (pintype "passive"))
      (node (ref "S27") (pin "2") (pinfunction "A_2") (pintype "passive"))
    )
    (net (code "60") (name "Net-(S27-B-Pad3)") (class "Default")
      (node (ref "S27") (pin "3") (pinfunction "B_3") (pintype "passive"))
      (node (ref "S27") (pin "4") (pinfunction "B_4") (pintype "passive"))
    )
    (net (code "61") (name "Net-(U1-CH0)") (class "Default")
      (node (ref "R9") (pin "1") (pinfunction "1_1") (pintype "passive"))
      (node (ref "S8") (pin "1") (pinfunction "A_1") (pintype "passive"))
      (node (ref "S8") (pin "2") (pinfunction "A_2") (pintype "passive"))
      (node (ref "U1") (pin "1") (pinfunction "CH0_1") (pintype "passive"))
    )
    (net (code "62") (name "Net-(U1-CH1)") (class "Default")
      (node (ref "R10") (pin "1") (pinfunction "1_1") (pintype "passive"))
      (node (ref "S7") (pin "1") (pinfunction "A_1") (pintype "passive"))
      (node (ref "S7") (pin "2") (pinfunction "A_2") (pintype "passive"))
      (node (ref "U1") (pin "2") (pinfunction "CH1_2") (pintype "passive"))
    )
    (net (code "63") (name "Net-(U1-CH2)") (class "Default")
      (node (ref "R8") (pin "1") (pinfunction "1_1") (pintype "passive"))
      (node (ref "S6") (pin "1") (pinfunction "A_1") (pintype "passive"))
      (node (ref "S6") (pin "2") (pinfunction "A_2") (pintype "passive"))
      (node (ref "U1") (pin "3") (pinfunction "CH2_3") (pintype "passive"))
    )
    (net (code "64") (name "Net-(U1-CH3)") (class "Default")
      (node (ref "R7") (pin "1") (pinfunction "1_1") (pintype "passive"))
      (node (ref "S5") (pin "1") (pinfunction "A_1") (pintype "passive"))
      (node (ref "S5") (pin "2") (pinfunction "A_2") (pintype "passive"))
      (node (ref "U1") (pin "4") (pinfunction "CH3_4") (pintype "passive"))
    )
    (net (code "65") (name "Net-(U1-CH4)") (class "Default")
      (node (ref "R6") (pin "1") (pinfunction "1_1") (pintype "passive"))
      (node (ref "S4") (pin "1") (pinfunction "A_1") (pintype "passive"))
      (node (ref "S4") (pin "2") (pinfunction "A_2") (pintype "passive"))
      (node (ref "U1") (pin "5") (pinfunction "CH4_5") (pintype "passive"))
    )
    (net (code "66") (name "Net-(U1-CH5)") (class "Default")
      (node (ref "R5") (pin "1") (pinfunction "1_1") (pintype "passive"))
      (node (ref "S3") (pin "1") (pinfunction "A_1") (pintype "passive"))
      (node (ref "S3") (pin "2") (pinfunction "A_2") (pintype "passive"))
      (node (ref "U1") (pin "6") (pinfunction "CH5_6") (pintype "passive"))
    )
    (net (code "67") (name "Net-(U1-CH6)") (class "Default")
      (node (ref "R4") (pin "1") (pinfunction "1_1") (pintype "passive"))
      (node (ref "S2") (pin "1") (pinfunction "A_1") (pintype "passive"))
      (node (ref "S2") (pin "2") (pinfunction "A_2") (pintype "passive"))
      (node (ref "U1") (pin "7") (pinfunction "CH6_7") (pintype "passive"))
    )
    (net (code "68") (name "Net-(U1-CH7)") (class "Default")
      (node (ref "R3") (pin "1") (pinfunction "1_1") (pintype "passive"))
      (node (ref "S1") (pin "1") (pinfunction "A_1") (pintype "passive"))
      (node (ref "S1") (pin "2") (pinfunction "A_2") (pintype "passive"))
      (node (ref "U1") (pin "8") (pinfunction "CH7_8") (pintype "passive"))
    )
    (net (code "69") (name "Net-(U2-CH0)") (class "Default")
      (node (ref "R16") (pin "1") (pinfunction "1_1") (pintype "passive"))
      (node (ref "S14") (pin "1") (pinfunction "A_1") (pintype "passive"))
      (node (ref "S14") (pin "2") (pinfunction "A_2") (pintype "passive"))
      (node (ref "U2") (pin "1") (pinfunction "CH0_1") (pintype "passive"))
    )
    (net (code "70") (name "Net-(U2-CH1)") (class "Default")
      (node (ref "R15") (pin "1") (pinfunction "1_1") (pintype "passive"))
      (node (ref "S13") (pin "1") (pinfunction "A_1") (pintype "passive"))
      (node (ref "S13") (pin "2") (pinfunction "A_2") (pintype "passive"))
      (node (ref "U2") (pin "2") (pinfunction "CH1_2") (pintype "passive"))
    )
    (net (code "71") (name "Net-(U2-CH2)") (class "Default")
      (node (ref "R14") (pin "1") (pinfunction "1_1") (pintype "passive"))
      (node (ref "S12") (pin "1") (pinfunction "A_1") (pintype "passive"))
      (node (ref "S12") (pin "2") (pinfunction "A_2") (pintype "passive"))
      (node (ref "U2") (pin "3") (pinfunction "CH2_3") (pintype "passive"))
    )
    (net (code "72") (name "Net-(U2-CH3)") (class "Default")
      (node (ref "R13") (pin "1") (pinfunction "1_1") (pintype "passive"))
      (node (ref "S11") (pin "1") (pinfunction "A_1") (pintype "passive"))
      (node (ref "S11") (pin "2") (pinfunction "A_2") (pintype "passive"))
      (node (ref "U2") (pin "4") (pinfunction "CH3_4") (pintype "passive"))
    )
    (net (code "73") (name "Net-(U2-CH4)") (class "Default")
      (node (ref "R12") (pin "1") (pinfunction "1_1") (pintype "passive"))
      (node (ref "S10") (pin "1") (pinfunction "A_1") (pintype "passive"))
      (node (ref "S10") (pin "2") (pinfunction "A_2") (pintype "passive"))
      (node (ref "U2") (pin "5") (pinfunction "CH4_5") (pintype "passive"))
    )
    (net (code "74") (name "Net-(U2-CH5)") (class "Default")
      (node (ref "R11") (pin "1") (pinfunction "1_1") (pintype "passive"))
      (node (ref "S9") (pin "1") (pinfunction "A_1") (pintype "passive"))
      (node (ref "S9") (pin "2") (pinfunction "A_2") (pintype "passive"))
      (node (ref "U2") (pin "6") (pinfunction "CH5_6") (pintype "passive"))
    )
    (net (code "75") (name "Net-(U3-CH0)") (class "Default")
      (node (ref "R29") (pin "1") (pinfunction "1_1") (pintype "passive"))
      (node (ref "S23") (pin "1") (pinfunction "A_1") (pintype "passive"))
      (node (ref "S23") (pin "2") (pinfunction "A_2") (pintype "passive"))
      (node (ref "U3") (pin "1") (pinfunction "CH0_1") (pintype "passive"))
    )
    (net (code "76") (name "Net-(U3-CH1)") (class "Default")
      (node (ref "R30") (pin "1") (pinfunction "1_1") (pintype "passive"))
      (node (ref "S22") (pin "1") (pinfunction "A_1") (pintype "passive"))
      (node (ref "S22") (pin "2") (pinfunction "A_2") (pintype "passive"))
      (node (ref "U3") (pin "2") (pinfunction "CH1_2") (pintype "passive"))
    )
    (net (code "77") (name "Net-(U3-CH2)") (class "Default")
      (node (ref "R31") (pin "1") (pinfunction "1_1") (pintype "passive"))
      (node (ref "S21") (pin "1") (pinfunction "A_1") (pintype "passive"))
      (node (ref "S21") (pin "2") (pinfunction "A_2") (pintype "passive"))
      (node (ref "U3") (pin "3") (pinfunction "CH2_3") (pintype "passive"))
    )
    (net (code "78") (name "Net-(U3-CH3)") (class "Default")
      (node (ref "R32") (pin "1") (pinfunction "1_1") (pintype "passive"))
      (node (ref "S20") (pin "1") (pinfunction "A_1") (pintype "passive"))
      (node (ref "S20") (pin "2") (pinfunction "A_2") (pintype "passive"))
      (node (ref "U3") (pin "4") (pinfunction "CH3_4") (pintype "passive"))
    )
    (net (code "79") (name "Net-(U3-CH4)") (class "Default")
      (node (ref "R33") (pin "1") (pinfunction "1_1") (pintype "passive"))
      (node (ref "S19") (pin "1") (pinfunction "A_1") (pintype "passive"))
      (node (ref "S19") (pin "2") (pinfunction "A_2") (pintype "passive"))
      (node (ref "U3") (pin "5") (pinfunction "CH4_5") (pintype "passive"))
    )
    (net (code "80") (name "Net-(U3-CH5)") (class "Default")
      (node (ref "R34") (pin "1") (pinfunction "1_1") (pintype "passive"))
      (node (ref "S18") (pin "1") (pinfunction "A_1") (pintype "passive"))
      (node (ref "S18") (pin "2") (pinfunction "A_2") (pintype "passive"))
      (node (ref "U3") (pin "6") (pinfunction "CH5_6") (pintype "passive"))
    )
    (net (code "81") (name "Net-(U3-CH6)") (class "Default")
      (node (ref "R35") (pin "1") (pinfunction "1_1") (pintype "passive"))
      (node (ref "S17") (pin "1") (pinfunction "A_1") (pintype "passive"))
      (node (ref "S17") (pin "2") (pinfunction "A_2") (pintype "passive"))
      (node (ref "U3") (pin "7") (pinfunction "CH6_7") (pintype "passive"))
    )
    (net (code "82") (name "Net-(U3-CH7)") (class "Default")
      (node (ref "R36") (pin "1") (pinfunction "1_1") (pintype "passive"))
      (node (ref "S16") (pin "1") (pinfunction "A_1") (pintype "passive"))
      (node (ref "S16") (pin "2") (pinfunction "A_2") (pintype "passive"))
      (node (ref "U3") (pin "8") (pinfunction "CH7_8") (pintype "passive"))
    )
    (net (code "83") (name "VCC12_IN") (class "Default")
      (node (ref "ACCUM") (pin "2") (pinfunction "2_2") (pintype "passive"))
      (node (ref "Q1") (pin "3") (pinfunction "S_3") (pintype "passive"))
      (node (ref "R26") (pin "2") (pinfunction "2_2") (pintype "passive"))
      (node (ref "R27") (pin "2") (pinfunction "2_2") (pintype "passive"))
      (node (ref "T1") (pin "LCP") (pinfunction "P2_LCP") (pintype "passive"))
    )
    (net (code "84") (name "unconnected-(ESP-8266-GPIO0-Pad3)") (class "Default")
      (node (ref "ESP-8266") (pin "3") (pinfunction "GPIO0_3") (pintype "passive"))
    )
    (net (code "85") (name "unconnected-(ESP-8266-GPIO2-Pad2)") (class "Default")
      (node (ref "ESP-8266") (pin "2") (pinfunction "GPIO2_2") (pintype "passive"))
    )
    (net (code "86") (name "unconnected-(ESP-8266-GPIO16-Pad7)") (class "Default")
      (node (ref "ESP-8266") (pin "7") (pinfunction "GPIO16_7") (pintype "passive"))
    )
    (net (code "87") (name "unconnected-(J2-DAT1-Pad8)") (class "Default")
      (node (ref "J2") (pin "8") (pinfunction "DAT1_8") (pintype "passive"))
    )
    (net (code "88") (name "unconnected-(J2-DAT2-Pad1)") (class "Default")
      (node (ref "J2") (pin "1") (pinfunction "DAT2_1") (pintype "passive"))
    )
    (net (code "89") (name "unconnected-(J2-PadMP3)") (class "Default")
      (node (ref "J2") (pin "MP3") (pinfunction "MP3_MP3") (pintype "passive"))
    )
    (net (code "90") (name "unconnected-(LCD-MODULE-NC-Pad23)") (class "Default")
      (node (ref "LCD-MODULE") (pin "23") (pinfunction "NC_23") (pintype "passive"))
    )
    (net (code "91") (name "unconnected-(LCD-MODULE-NC-Pad24)") (class "Default")
      (node (ref "LCD-MODULE") (pin "24") (pinfunction "NC_24") (pintype "passive"))
    )
    (net (code "92") (name "unconnected-(LCD-MODULE-NC-Pad25)") (class "Default")
      (node (ref "LCD-MODULE") (pin "25") (pinfunction "NC_25") (pintype "passive"))
    )
    (net (code "93") (name "unconnected-(LCD-MODULE-NC-Pad27)") (class "Default")
      (node (ref "LCD-MODULE") (pin "27") (pinfunction "NC_27") (pintype "passive"))
    )
    (net (code "94") (name "unconnected-(LCD-MODULE-NC-Pad28)") (class "Default")
      (node (ref "LCD-MODULE") (pin "28") (pinfunction "NC_28") (pintype "passive"))
    )
    (net (code "95") (name "unconnected-(LCD-MODULE-NC-Pad29)") (class "Default")
      (node (ref "LCD-MODULE") (pin "29") (pinfunction "NC_29") (pintype "passive"))
    )
    (net (code "96") (name "unconnected-(LCD-MODULE-NC-Pad30)") (class "Default")
      (node (ref "LCD-MODULE") (pin "30") (pinfunction "NC_30") (pintype "passive"))
    )
    (net (code "97") (name "unconnected-(LCD-MODULE-RESET-Pad37)") (class "Default")
      (node (ref "LCD-MODULE") (pin "37") (pinfunction "RESET_37") (pintype "passive"))
    )
    (net (code "98") (name "unconnected-(LCD-MODULE-SD_CLK-Pad33)") (class "Default")
      (node (ref "LCD-MODULE") (pin "33") (pinfunction "SD_CLK_33") (pintype "passive"))
    )
    (net (code "99") (name "unconnected-(LCD-MODULE-SD_CS-Pad34)") (class "Default")
      (node (ref "LCD-MODULE") (pin "34") (pinfunction "SD_CS_34") (pintype "passive"))
    )
    (net (code "100") (name "unconnected-(LCD-MODULE-SD_MISO-Pad31)") (class "Default")
      (node (ref "LCD-MODULE") (pin "31") (pinfunction "SD_MISO_31") (pintype "passive"))
    )
    (net (code "101") (name "unconnected-(LCD-MODULE-SD_MOSI-Pad32)") (class "Default")
      (node (ref "LCD-MODULE") (pin "32") (pinfunction "SD_MOSI_32") (pintype "passive"))
    )
  )
)
